# ex_v2.net
KiCad netlist of a schematic drawn in EAGLE
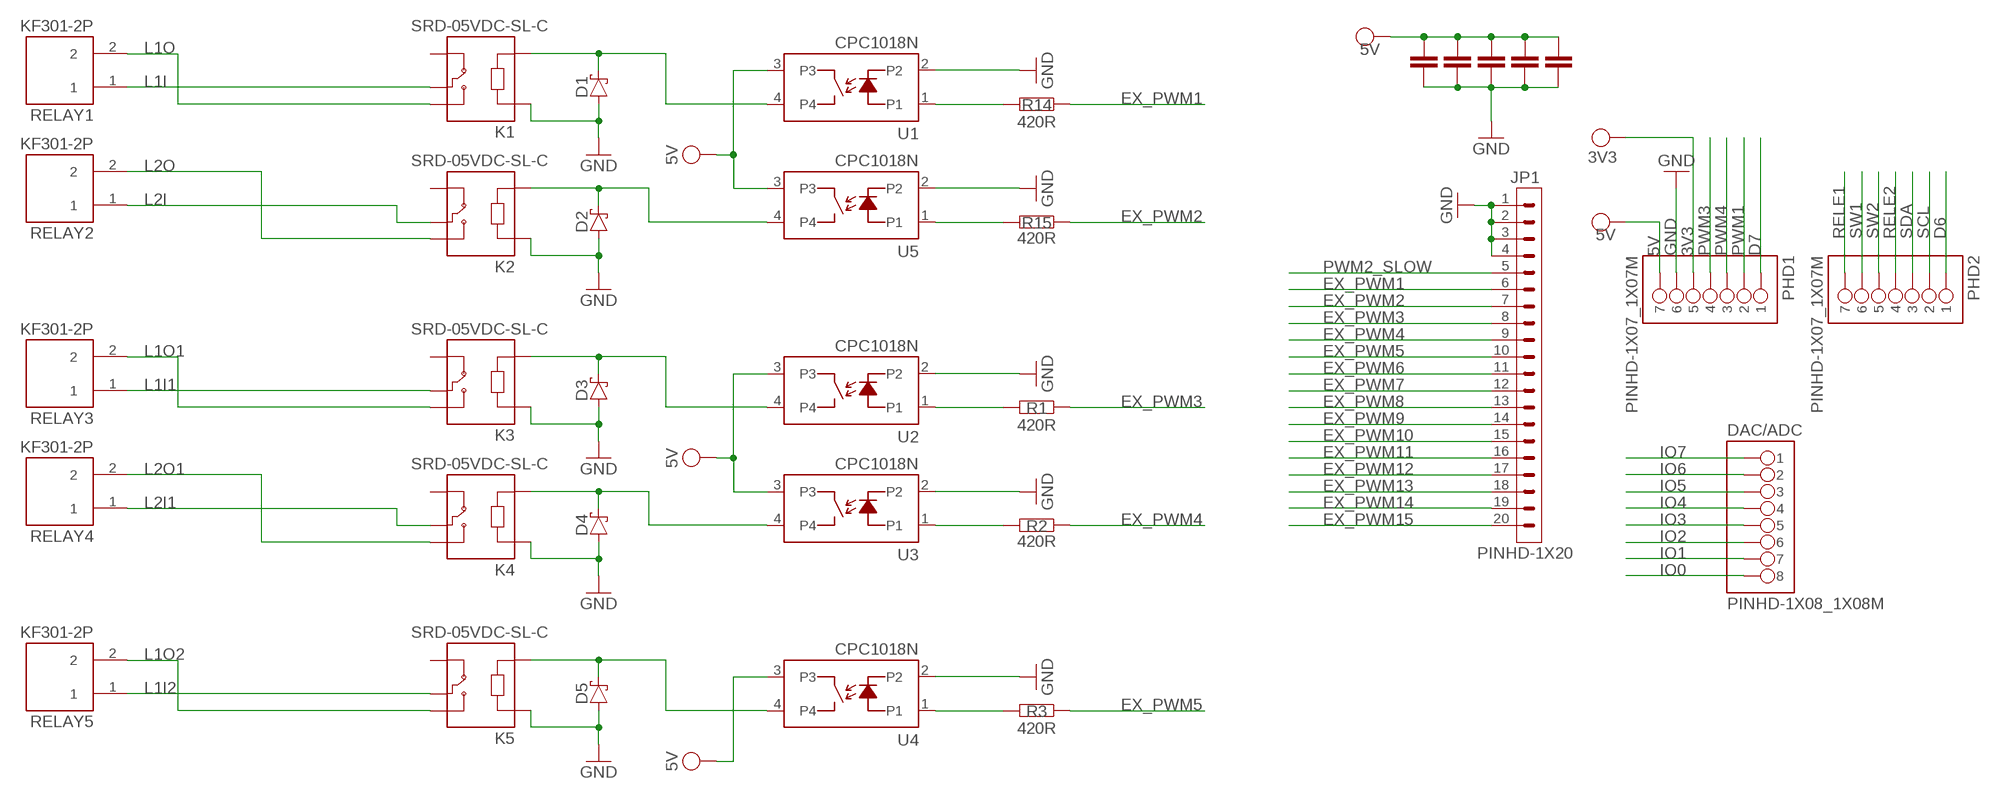
[diagram p0: schematic, sheet 1]

(export (version "E")
  (design (tool "Eeschema 10.0.6"))
  (components
    (comp (ref "C1")
      (value "10uF")
      (footprint "eagle-import:CAPC2012X110")
      (libsource (lib "eagle-import") (part "CCHIP-0805(2012-METRIC)_"))
    )
    (comp (ref "C2")
      (value "10uF")
      (footprint "eagle-import:CAPC2012X110")
      (libsource (lib "eagle-import") (part "CCHIP-0805(2012-METRIC)_"))
    )
    (comp (ref "C3")
      (value "10uF")
      (footprint "eagle-import:CAPC2012X110")
      (libsource (lib "eagle-import") (part "CCHIP-0805(2012-METRIC)_"))
    )
    (comp (ref "C6")
      (value "10uF")
      (footprint "eagle-import:CAPC2012X110")
      (libsource (lib "eagle-import") (part "CCHIP-0805(2012-METRIC)_"))
    )
    (comp (ref "C8")
      (value "10uF")
      (footprint "eagle-import:CAPC2012X110")
      (libsource (lib "eagle-import") (part "CCHIP-0805(2012-METRIC)_"))
    )
    (comp (ref "D1")
      (value "SCHOTTKY_MBR0520LT1GDO-219")
      (footprint "eagle-import:SODFL3718X115")
      (fields (field (name "MANUFACTURER") "onsemi") (field (name "MPN") "MBR0520LT1G"))
      (libsource (lib "eagle-import") (part "SCHOTTKY_DO-219MBR0520LT1G"))
    )
    (comp (ref "D2")
      (value "SCHOTTKY_MBR0520LT1GDO-219")
      (footprint "eagle-import:SODFL3718X115")
      (fields (field (name "MANUFACTURER") "onsemi") (field (name "MPN") "MBR0520LT1G"))
      (libsource (lib "eagle-import") (part "SCHOTTKY_DO-219MBR0520LT1G"))
    )
    (comp (ref "D3")
      (value "SCHOTTKY_MBR0520LT1GDO-219")
      (footprint "eagle-import:SODFL3718X115")
      (fields (field (name "MANUFACTURER") "onsemi") (field (name "MPN") "MBR0520LT1G"))
      (libsource (lib "eagle-import") (part "SCHOTTKY_DO-219MBR0520LT1G"))
    )
    (comp (ref "D4")
      (value "SCHOTTKY_MBR0520LT1GDO-219")
      (footprint "eagle-import:SODFL3718X115")
      (fields (field (name "MANUFACTURER") "onsemi") (field (name "MPN") "MBR0520LT1G"))
      (libsource (lib "eagle-import") (part "SCHOTTKY_DO-219MBR0520LT1G"))
    )
    (comp (ref "D5")
      (value "SCHOTTKY_MBR0520LT1GDO-219")
      (footprint "eagle-import:SODFL3718X115")
      (fields (field (name "MANUFACTURER") "onsemi") (field (name "MPN") "MBR0520LT1G"))
      (libsource (lib "eagle-import") (part "SCHOTTKY_DO-219MBR0520LT1G"))
    )
    (comp (ref "DAC/ADC")
      (value "PINHD-1X08_1X08M")
      (footprint "eagle-import:1X08")
      (libsource (lib "eagle-import") (part "PINHD-1X08_1X08M"))
    )
    (comp (ref "JP1")
      (value "PINHD-1X20")
      (footprint "eagle-import:1X20")
      (libsource (lib "eagle-import") (part "PINHD-1X20"))
    )
    (comp (ref "K1")
      (value "SRD-05VDC-SL-C")
      (footprint "eagle-import:RELAY_SRD-05VDC-SL-C")
      (fields (field (name "MF") "Songle Relay"))
      (libsource (lib "eagle-import") (part "SRD-05VDC-SL-C"))
    )
    (comp (ref "K2")
      (value "SRD-05VDC-SL-C")
      (footprint "eagle-import:RELAY_SRD-05VDC-SL-C")
      (fields (field (name "MF") "Songle Relay"))
      (libsource (lib "eagle-import") (part "SRD-05VDC-SL-C"))
    )
    (comp (ref "K3")
      (value "SRD-05VDC-SL-C")
      (footprint "eagle-import:RELAY_SRD-05VDC-SL-C")
      (fields (field (name "MF") "Songle Relay"))
      (libsource (lib "eagle-import") (part "SRD-05VDC-SL-C"))
    )
    (comp (ref "K4")
      (value "SRD-05VDC-SL-C")
      (footprint "eagle-import:RELAY_SRD-05VDC-SL-C")
      (fields (field (name "MF") "Songle Relay"))
      (libsource (lib "eagle-import") (part "SRD-05VDC-SL-C"))
    )
    (comp (ref "K5")
      (value "SRD-05VDC-SL-C")
      (footprint "eagle-import:RELAY_SRD-05VDC-SL-C")
      (fields (field (name "MF") "Songle Relay"))
      (libsource (lib "eagle-import") (part "SRD-05VDC-SL-C"))
    )
    (comp (ref "PHD1")
      (value "PINHD-1X07_1X07M")
      (footprint "eagle-import:1X07")
      (libsource (lib "eagle-import") (part "PINHD-1X07_1X07M"))
    )
    (comp (ref "PHD2")
      (value "PINHD-1X07_1X07M")
      (footprint "eagle-import:1X07")
      (libsource (lib "eagle-import") (part "PINHD-1X07_1X07M"))
    )
    (comp (ref "R1")
      (value "420R")
      (footprint "eagle-import:RESC1608X60")
      (libsource (lib "eagle-import") (part "RCHIP-0603(1608-METRIC)_"))
    )
    (comp (ref "R2")
      (value "420R")
      (footprint "eagle-import:RESC1608X60")
      (libsource (lib "eagle-import") (part "RCHIP-0603(1608-METRIC)_"))
    )
    (comp (ref "R3")
      (value "420R")
      (footprint "eagle-import:RESC1608X60")
      (libsource (lib "eagle-import") (part "RCHIP-0603(1608-METRIC)_"))
    )
    (comp (ref "R14")
      (value "420R")
      (footprint "eagle-import:RESC1608X60")
      (libsource (lib "eagle-import") (part "RCHIP-0603(1608-METRIC)_"))
    )
    (comp (ref "R15")
      (value "420R")
      (footprint "eagle-import:RESC1608X60")
      (libsource (lib "eagle-import") (part "RCHIP-0603(1608-METRIC)_"))
    )
    (comp (ref "RELAY1")
      (value "KF301-2P")
      (footprint "eagle-import:HANDSON_KF301-2P")
      (fields (field (name "MF") "Handson Technology"))
      (libsource (lib "eagle-import") (part "KF301-2P"))
    )
    (comp (ref "RELAY2")
      (value "KF301-2P")
      (footprint "eagle-import:HANDSON_KF301-2P")
      (fields (field (name "MF") "Handson Technology"))
      (libsource (lib "eagle-import") (part "KF301-2P"))
    )
    (comp (ref "RELAY3")
      (value "KF301-2P")
      (footprint "eagle-import:HANDSON_KF301-2P")
      (fields (field (name "MF") "Handson Technology"))
      (libsource (lib "eagle-import") (part "KF301-2P"))
    )
    (comp (ref "RELAY4")
      (value "KF301-2P")
      (footprint "eagle-import:HANDSON_KF301-2P")
      (fields (field (name "MF") "Handson Technology"))
      (libsource (lib "eagle-import") (part "KF301-2P"))
    )
    (comp (ref "RELAY5")
      (value "KF301-2P")
      (footprint "eagle-import:HANDSON_KF301-2P")
      (fields (field (name "MF") "Handson Technology"))
      (libsource (lib "eagle-import") (part "KF301-2P"))
    )
    (comp (ref "U1")
      (value "CPC1018N")
      (footprint "eagle-import:CLARE_SO4")
      (fields (field (name "MF") "IXYS Integrated Circuits"))
      (libsource (lib "eagle-import") (part "CPC1018N"))
    )
    (comp (ref "U2")
      (value "CPC1018N")
      (footprint "eagle-import:CLARE_SO4")
      (fields (field (name "MF") "IXYS Integrated Circuits"))
      (libsource (lib "eagle-import") (part "CPC1018N"))
    )
    (comp (ref "U3")
      (value "CPC1018N")
      (footprint "eagle-import:CLARE_SO4")
      (fields (field (name "MF") "IXYS Integrated Circuits"))
      (libsource (lib "eagle-import") (part "CPC1018N"))
    )
    (comp (ref "U4")
      (value "CPC1018N")
      (footprint "eagle-import:CLARE_SO4")
      (fields (field (name "MF") "IXYS Integrated Circuits"))
      (libsource (lib "eagle-import") (part "CPC1018N"))
    )
    (comp (ref "U5")
      (value "CPC1018N")
      (footprint "eagle-import:CLARE_SO4")
      (fields (field (name "MF") "IXYS Integrated Circuits"))
      (libsource (lib "eagle-import") (part "CPC1018N"))
    )
  )
  (nets
    (net (code "1") (name "/D6") (class "Default")
      (node (ref "PHD2") (pin "1") (pinfunction "1_1") (pintype "bidirectional"))
    )
    (net (code "2") (name "/D7") (class "Default")
      (node (ref "PHD1") (pin "1") (pinfunction "1_1") (pintype "bidirectional"))
    )
    (net (code "3") (name "/EX_PWM1") (class "Default")
      (node (ref "JP1") (pin "6") (pinfunction "6_6") (pintype "passive"))
      (node (ref "R14") (pin "1") (pinfunction "1_1") (pintype "passive"))
    )
    (net (code "4") (name "/EX_PWM2") (class "Default")
      (node (ref "JP1") (pin "7") (pinfunction "7_7") (pintype "passive"))
      (node (ref "R15") (pin "1") (pinfunction "1_1") (pintype "passive"))
    )
    (net (code "5") (name "/EX_PWM3") (class "Default")
      (node (ref "JP1") (pin "8") (pinfunction "8_8") (pintype "passive"))
      (node (ref "R1") (pin "1") (pinfunction "1_1") (pintype "passive"))
    )
    (net (code "6") (name "/EX_PWM4") (class "Default")
      (node (ref "JP1") (pin "9") (pinfunction "9_9") (pintype "passive"))
      (node (ref "R2") (pin "1") (pinfunction "1_1") (pintype "passive"))
    )
    (net (code "7") (name "/EX_PWM5") (class "Default")
      (node (ref "JP1") (pin "10") (pinfunction "10_10") (pintype "passive"))
      (node (ref "R3") (pin "1") (pinfunction "1_1") (pintype "passive"))
    )
    (net (code "8") (name "/EX_PWM6") (class "Default")
      (node (ref "JP1") (pin "11") (pinfunction "11_11") (pintype "passive"))
    )
    (net (code "9") (name "/EX_PWM7") (class "Default")
      (node (ref "JP1") (pin "12") (pinfunction "12_12") (pintype "passive"))
    )
    (net (code "10") (name "/EX_PWM8") (class "Default")
      (node (ref "JP1") (pin "13") (pinfunction "13_13") (pintype "passive"))
    )
    (net (code "11") (name "/EX_PWM9") (class "Default")
      (node (ref "JP1") (pin "14") (pinfunction "14_14") (pintype "passive"))
    )
    (net (code "12") (name "/EX_PWM10") (class "Default")
      (node (ref "JP1") (pin "15") (pinfunction "15_15") (pintype "passive"))
    )
    (net (code "13") (name "/EX_PWM11") (class "Default")
      (node (ref "JP1") (pin "16") (pinfunction "16_16") (pintype "passive"))
    )
    (net (code "14") (name "/EX_PWM12") (class "Default")
      (node (ref "JP1") (pin "17") (pinfunction "17_17") (pintype "passive"))
    )
    (net (code "15") (name "/EX_PWM13") (class "Default")
      (node (ref "JP1") (pin "18") (pinfunction "18_18") (pintype "passive"))
    )
    (net (code "16") (name "/EX_PWM14") (class "Default")
      (node (ref "JP1") (pin "19") (pinfunction "19_19") (pintype "passive"))
    )
    (net (code "17") (name "/EX_PWM15") (class "Default")
      (node (ref "JP1") (pin "20") (pinfunction "20_20") (pintype "passive"))
    )
    (net (code "18") (name "/IO0") (class "Default")
      (node (ref "DAC/ADC") (pin "8") (pinfunction "8_8") (pintype "bidirectional"))
    )
    (net (code "19") (name "/IO1") (class "Default")
      (node (ref "DAC/ADC") (pin "7") (pinfunction "7_7") (pintype "bidirectional"))
    )
    (net (code "20") (name "/IO2") (class "Default")
      (node (ref "DAC/ADC") (pin "6") (pinfunction "6_6") (pintype "bidirectional"))
    )
    (net (code "21") (name "/IO3") (class "Default")
      (node (ref "DAC/ADC") (pin "5") (pinfunction "5_5") (pintype "bidirectional"))
    )
    (net (code "22") (name "/IO4") (class "Default")
      (node (ref "DAC/ADC") (pin "4") (pinfunction "4_4") (pintype "bidirectional"))
    )
    (net (code "23") (name "/IO5") (class "Default")
      (node (ref "DAC/ADC") (pin "3") (pinfunction "3_3") (pintype "bidirectional"))
    )
    (net (code "24") (name "/IO6") (class "Default")
      (node (ref "DAC/ADC") (pin "2") (pinfunction "2_2") (pintype "bidirectional"))
    )
    (net (code "25") (name "/IO7") (class "Default")
      (node (ref "DAC/ADC") (pin "1") (pinfunction "1_1") (pintype "bidirectional"))
    )
    (net (code "26") (name "/L1I") (class "Default")
      (node (ref "K1") (pin "COM") (pinfunction "COM_COM") (pintype "passive"))
      (node (ref "RELAY1") (pin "1") (pinfunction "1_1") (pintype "passive"))
    )
    (net (code "27") (name "/L1I1") (class "Default")
      (node (ref "K3") (pin "COM") (pinfunction "COM_COM") (pintype "passive"))
      (node (ref "RELAY3") (pin "1") (pinfunction "1_1") (pintype "passive"))
    )
    (net (code "28") (name "/L1I2") (class "Default")
      (node (ref "K5") (pin "COM") (pinfunction "COM_COM") (pintype "passive"))
      (node (ref "RELAY5") (pin "1") (pinfunction "1_1") (pintype "passive"))
    )
    (net (code "29") (name "/L1O") (class "Default")
      (node (ref "K1") (pin "NO") (pinfunction "NO_NO") (pintype "passive"))
      (node (ref "RELAY1") (pin "2") (pinfunction "2_2") (pintype "passive"))
    )
    (net (code "30") (name "/L1O1") (class "Default")
      (node (ref "K3") (pin "NO") (pinfunction "NO_NO") (pintype "passive"))
      (node (ref "RELAY3") (pin "2") (pinfunction "2_2") (pintype "passive"))
    )
    (net (code "31") (name "/L1O2") (class "Default")
      (node (ref "K5") (pin "NO") (pinfunction "NO_NO") (pintype "passive"))
      (node (ref "RELAY5") (pin "2") (pinfunction "2_2") (pintype "passive"))
    )
    (net (code "32") (name "/L2I") (class "Default")
      (node (ref "K2") (pin "COM") (pinfunction "COM_COM") (pintype "passive"))
      (node (ref "RELAY2") (pin "1") (pinfunction "1_1") (pintype "passive"))
    )
    (net (code "33") (name "/L2I1") (class "Default")
      (node (ref "K4") (pin "COM") (pinfunction "COM_COM") (pintype "passive"))
      (node (ref "RELAY4") (pin "1") (pinfunction "1_1") (pintype "passive"))
    )
    (net (code "34") (name "/L2O") (class "Default")
      (node (ref "K2") (pin "NO") (pinfunction "NO_NO") (pintype "passive"))
      (node (ref "RELAY2") (pin "2") (pinfunction "2_2") (pintype "passive"))
    )
    (net (code "35") (name "/L2O1") (class "Default")
      (node (ref "K4") (pin "NO") (pinfunction "NO_NO") (pintype "passive"))
      (node (ref "RELAY4") (pin "2") (pinfunction "2_2") (pintype "passive"))
    )
    (net (code "36") (name "/PWM1") (class "Default")
      (node (ref "PHD1") (pin "2") (pinfunction "2_2") (pintype "bidirectional"))
    )
    (net (code "37") (name "/PWM2_SLOW") (class "Default")
      (node (ref "JP1") (pin "5") (pinfunction "5_5") (pintype "passive"))
    )
    (net (code "38") (name "/PWM3") (class "Default")
      (node (ref "PHD1") (pin "4") (pinfunction "4_4") (pintype "bidirectional"))
    )
    (net (code "39") (name "/PWM4") (class "Default")
      (node (ref "PHD1") (pin "3") (pinfunction "3_3") (pintype "bidirectional"))
    )
    (net (code "40") (name "/RELE1") (class "Default")
      (node (ref "PHD2") (pin "7") (pinfunction "7_7") (pintype "bidirectional"))
    )
    (net (code "41") (name "/RELE2") (class "Default")
      (node (ref "PHD2") (pin "4") (pinfunction "4_4") (pintype "bidirectional"))
    )
    (net (code "42") (name "/SCL") (class "Default")
      (node (ref "PHD2") (pin "2") (pinfunction "2_2") (pintype "bidirectional"))
    )
    (net (code "43") (name "/SDA") (class "Default")
      (node (ref "PHD2") (pin "3") (pinfunction "3_3") (pintype "bidirectional"))
    )
    (net (code "44") (name "/SW1") (class "Default")
      (node (ref "PHD2") (pin "6") (pinfunction "6_6") (pintype "bidirectional"))
    )
    (net (code "45") (name "/SW2") (class "Default")
      (node (ref "PHD2") (pin "5") (pinfunction "5_5") (pintype "bidirectional"))
    )
    (net (code "46") (name "3V3") (class "Default")
      (node (ref "PHD1") (pin "5") (pinfunction "5_5") (pintype "bidirectional"))
    )
    (net (code "47") (name "5V") (class "Default")
      (node (ref "C1") (pin "1") (pinfunction "1_1") (pintype "passive"))
      (node (ref "C2") (pin "1") (pinfunction "1_1") (pintype "passive"))
      (node (ref "C3") (pin "1") (pinfunction "1_1") (pintype "passive"))
      (node (ref "C6") (pin "1") (pinfunction "1_1") (pintype "passive"))
      (node (ref "C8") (pin "1") (pinfunction "1_1") (pintype "passive"))
      (node (ref "PHD1") (pin "7") (pinfunction "7_7") (pintype "bidirectional"))
      (node (ref "U1") (pin "3") (pinfunction "P3_3") (pintype "passive"))
      (node (ref "U2") (pin "3") (pinfunction "P3_3") (pintype "passive"))
      (node (ref "U3") (pin "3") (pinfunction "P3_3") (pintype "passive"))
      (node (ref "U4") (pin "3") (pinfunction "P3_3") (pintype "passive"))
      (node (ref "U5") (pin "3") (pinfunction "P3_3") (pintype "passive"))
    )
    (net (code "48") (name "GND") (class "Default")
      (node (ref "C1") (pin "2") (pinfunction "2_2") (pintype "passive"))
      (node (ref "C2") (pin "2") (pinfunction "2_2") (pintype "passive"))
      (node (ref "C3") (pin "2") (pinfunction "2_2") (pintype "passive"))
      (node (ref "C6") (pin "2") (pinfunction "2_2") (pintype "passive"))
      (node (ref "C8") (pin "2") (pinfunction "2_2") (pintype "passive"))
      (node (ref "D1") (pin "2") (pinfunction "A_2") (pintype "passive"))
      (node (ref "D2") (pin "2") (pinfunction "A_2") (pintype "passive"))
      (node (ref "D3") (pin "2") (pinfunction "A_2") (pintype "passive"))
      (node (ref "D4") (pin "2") (pinfunction "A_2") (pintype "passive"))
      (node (ref "D5") (pin "2") (pinfunction "A_2") (pintype "passive"))
      (node (ref "JP1") (pin "1") (pinfunction "1_1") (pintype "passive"))
      (node (ref "JP1") (pin "2") (pinfunction "2_2") (pintype "passive"))
      (node (ref "JP1") (pin "3") (pinfunction "3_3") (pintype "passive"))
      (node (ref "JP1") (pin "4") (pinfunction "4_4") (pintype "passive"))
      (node (ref "K1") (pin "A1") (pinfunction "A1_A1") (pintype "passive"))
      (node (ref "K2") (pin "A1") (pinfunction "A1_A1") (pintype "passive"))
      (node (ref "K3") (pin "A1") (pinfunction "A1_A1") (pintype "passive"))
      (node (ref "K4") (pin "A1") (pinfunction "A1_A1") (pintype "passive"))
      (node (ref "K5") (pin "A1") (pinfunction "A1_A1") (pintype "passive"))
      (node (ref "PHD1") (pin "6") (pinfunction "6_6") (pintype "bidirectional"))
      (node (ref "U1") (pin "2") (pinfunction "P2_2") (pintype "passive"))
      (node (ref "U2") (pin "2") (pinfunction "P2_2") (pintype "passive"))
      (node (ref "U3") (pin "2") (pinfunction "P2_2") (pintype "passive"))
      (node (ref "U4") (pin "2") (pinfunction "P2_2") (pintype "passive"))
      (node (ref "U5") (pin "2") (pinfunction "P2_2") (pintype "passive"))
    )
    (net (code "49") (name "Net-(D1-C)") (class "Default")
      (node (ref "D1") (pin "1") (pinfunction "C_1") (pintype "passive"))
      (node (ref "K1") (pin "A2") (pinfunction "A2_A2") (pintype "passive"))
      (node (ref "U1") (pin "4") (pinfunction "P4_4") (pintype "passive"))
    )
    (net (code "50") (name "Net-(D2-C)") (class "Default")
      (node (ref "D2") (pin "1") (pinfunction "C_1") (pintype "passive"))
      (node (ref "K2") (pin "A2") (pinfunction "A2_A2") (pintype "passive"))
      (node (ref "U5") (pin "4") (pinfunction "P4_4") (pintype "passive"))
    )
    (net (code "51") (name "Net-(D3-C)") (class "Default")
      (node (ref "D3") (pin "1") (pinfunction "C_1") (pintype "passive"))
      (node (ref "K3") (pin "A2") (pinfunction "A2_A2") (pintype "passive"))
      (node (ref "U2") (pin "4") (pinfunction "P4_4") (pintype "passive"))
    )
    (net (code "52") (name "Net-(D4-C)") (class "Default")
      (node (ref "D4") (pin "1") (pinfunction "C_1") (pintype "passive"))
      (node (ref "K4") (pin "A2") (pinfunction "A2_A2") (pintype "passive"))
      (node (ref "U3") (pin "4") (pinfunction "P4_4") (pintype "passive"))
    )
    (net (code "53") (name "Net-(D5-C)") (class "Default")
      (node (ref "D5") (pin "1") (pinfunction "C_1") (pintype "passive"))
      (node (ref "K5") (pin "A2") (pinfunction "A2_A2") (pintype "passive"))
      (node (ref "U4") (pin "4") (pinfunction "P4_4") (pintype "passive"))
    )
    (net (code "54") (name "Net-(U1-P1)") (class "Default")
      (node (ref "R14") (pin "2") (pinfunction "2_2") (pintype "passive"))
      (node (ref "U1") (pin "1") (pinfunction "P1_1") (pintype "passive"))
    )
    (net (code "55") (name "Net-(U2-P1)") (class "Default")
      (node (ref "R1") (pin "2") (pinfunction "2_2") (pintype "passive"))
      (node (ref "U2") (pin "1") (pinfunction "P1_1") (pintype "passive"))
    )
    (net (code "56") (name "Net-(U3-P1)") (class "Default")
      (node (ref "R2") (pin "2") (pinfunction "2_2") (pintype "passive"))
      (node (ref "U3") (pin "1") (pinfunction "P1_1") (pintype "passive"))
    )
    (net (code "57") (name "Net-(U4-P1)") (class "Default")
      (node (ref "R3") (pin "2") (pinfunction "2_2") (pintype "passive"))
      (node (ref "U4") (pin "1") (pinfunction "P1_1") (pintype "passive"))
    )
    (net (code "58") (name "Net-(U5-P1)") (class "Default")
      (node (ref "R15") (pin "2") (pinfunction "2_2") (pintype "passive"))
      (node (ref "U5") (pin "1") (pinfunction "P1_1") (pintype "passive"))
    )
    (net (code "59") (name "unconnected-(K1-PadNC)") (class "Default")
      (node (ref "K1") (pin "NC") (pinfunction "NC_NC") (pintype "passive"))
    )
    (net (code "60") (name "unconnected-(K2-PadNC)") (class "Default")
      (node (ref "K2") (pin "NC") (pinfunction "NC_NC") (pintype "passive"))
    )
    (net (code "61") (name "unconnected-(K3-PadNC)") (class "Default")
      (node (ref "K3") (pin "NC") (pinfunction "NC_NC") (pintype "passive"))
    )
    (net (code "62") (name "unconnected-(K4-PadNC)") (class "Default")
      (node (ref "K4") (pin "NC") (pinfunction "NC_NC") (pintype "passive"))
    )
    (net (code "63") (name "unconnected-(K5-PadNC)") (class "Default")
      (node (ref "K5") (pin "NC") (pinfunction "NC_NC") (pintype "passive"))
    )
  )
)
